# Main.net
KiCad netlist of a schematic drawn in Altium Designer
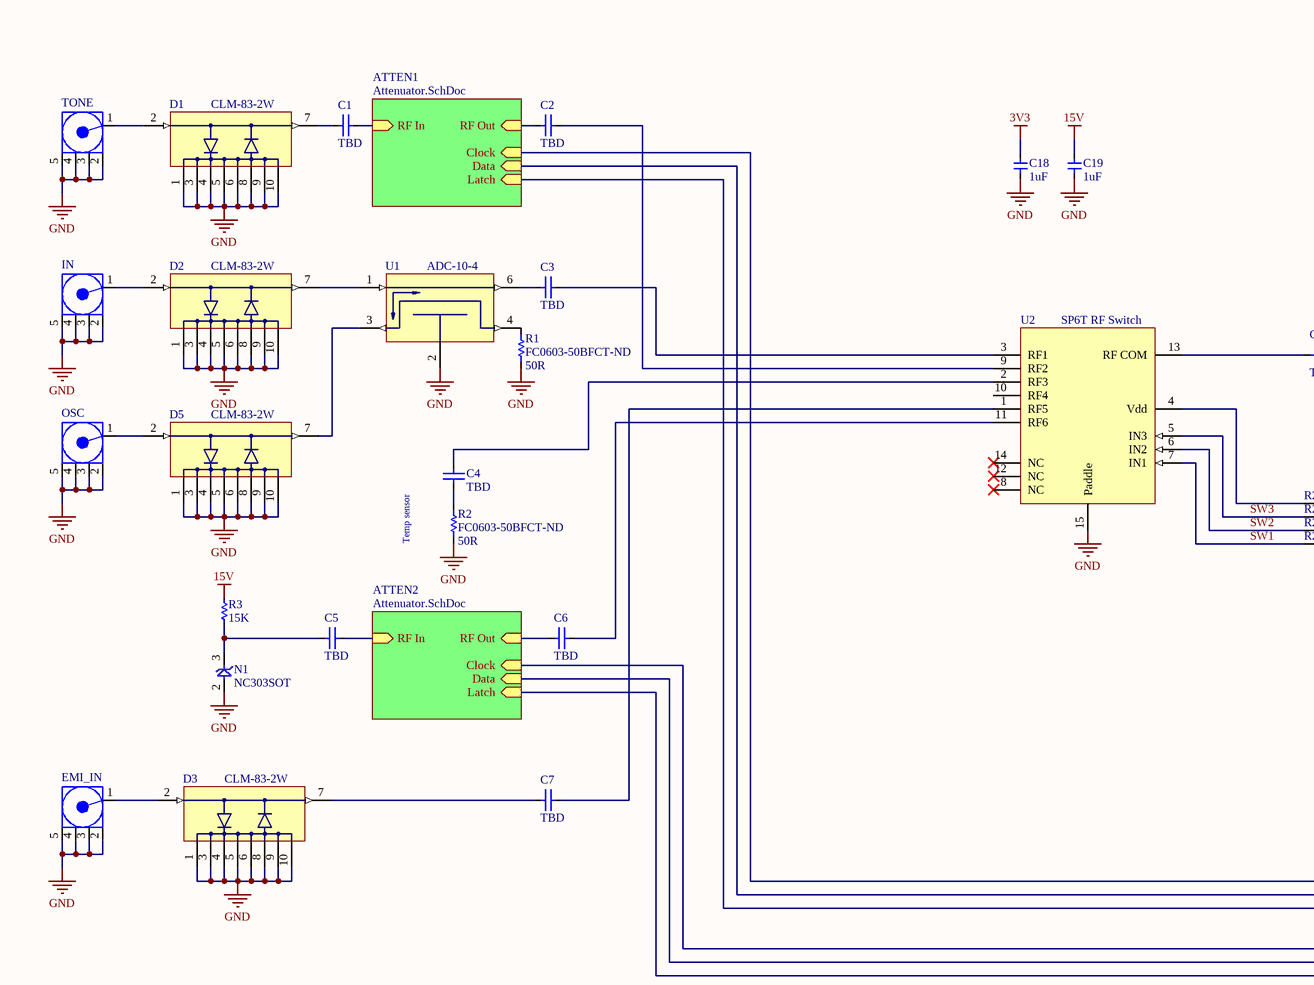
[diagram p0: Main.SchDoc, left]
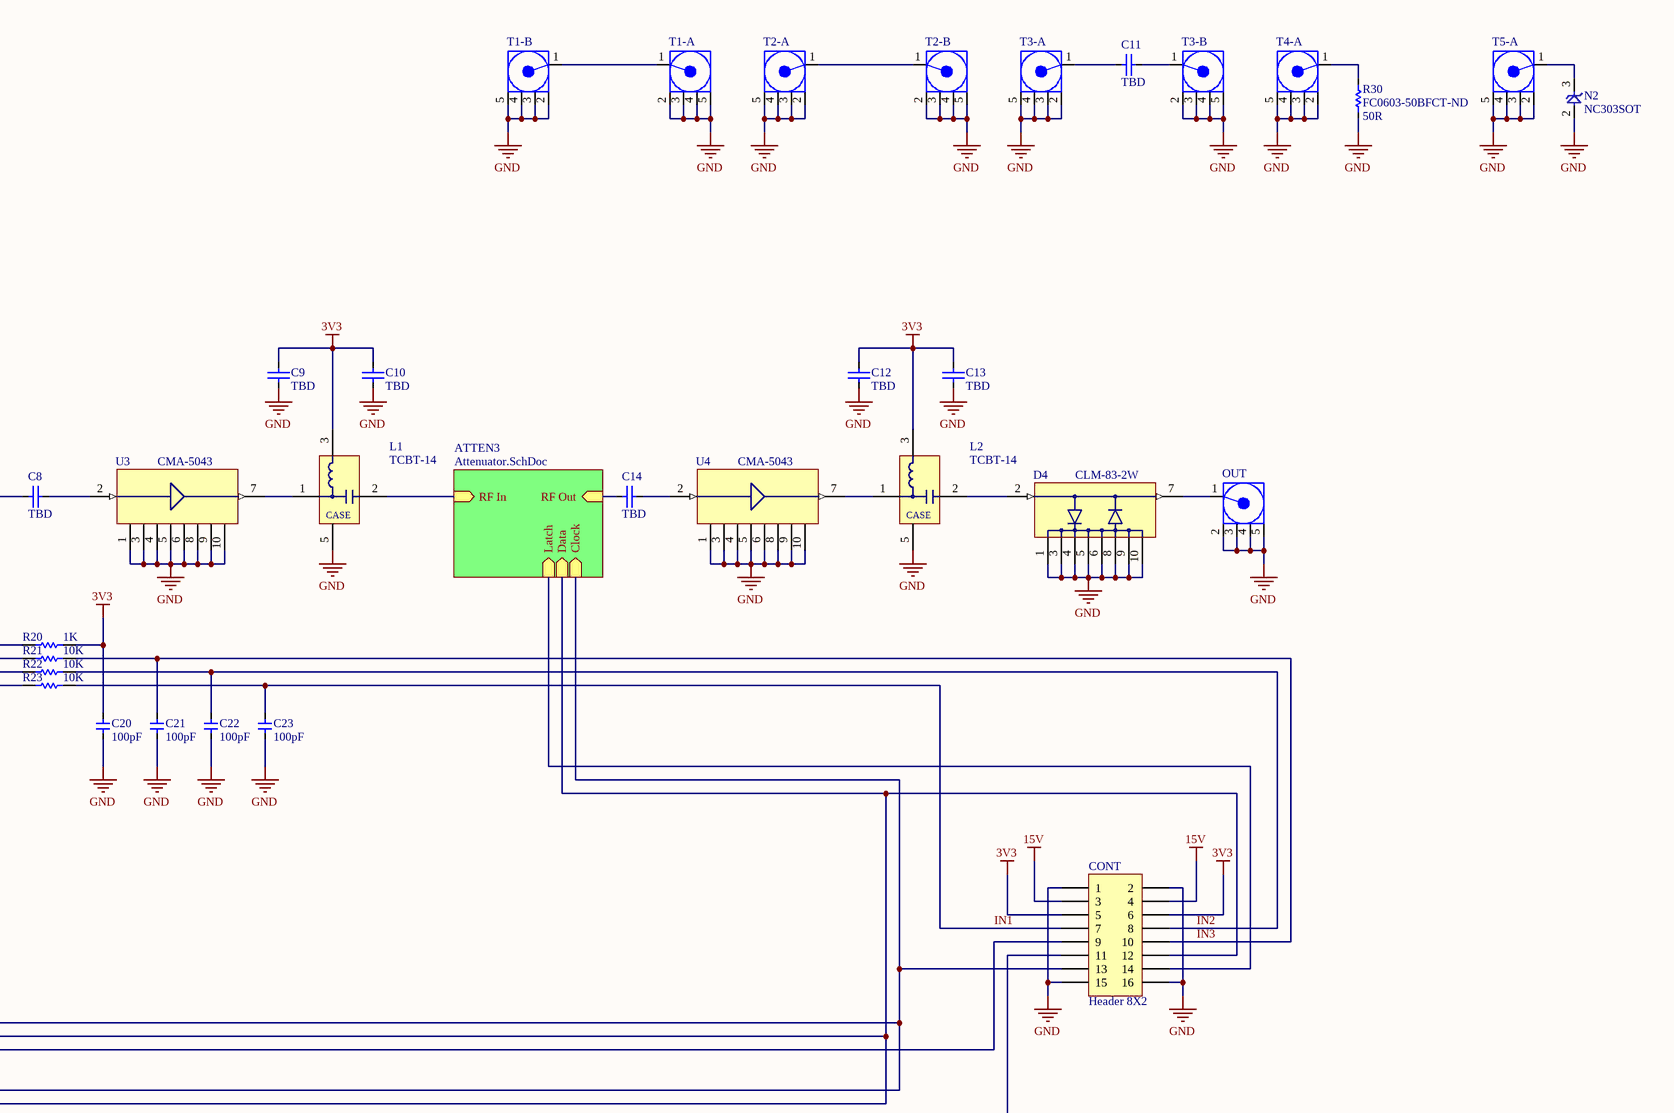
[diagram p1: Main.SchDoc, right]

(export (version "E")
  (design (tool "Eeschema 10.0.6"))
  (components
    (comp (ref "C1")
      (value "TBD")
      (footprint "0402C")
      (description "Capacitor")
      (fields (field (name "Comment") "Cap") (field (name "PUBLISHER") "Altium Limited"))
      (libsource (lib "Miscellaneous Devices") (part "Cap"))
    )
    (comp (ref "C2")
      (value "TBD")
      (footprint "0402C")
      (description "Capacitor")
      (fields (field (name "Comment") "Cap") (field (name "PUBLISHER") "Altium Limited"))
      (libsource (lib "Miscellaneous Devices") (part "Cap"))
    )
    (comp (ref "C3")
      (value "TBD")
      (footprint "0402C")
      (description "Capacitor")
      (fields (field (name "Comment") "Cap") (field (name "PUBLISHER") "Altium Limited"))
      (libsource (lib "Miscellaneous Devices") (part "Cap"))
    )
    (comp (ref "C4")
      (value "TBD")
      (footprint "0402C")
      (description "Capacitor")
      (fields (field (name "Comment") "Cap") (field (name "PUBLISHER") "Altium Limited"))
      (libsource (lib "Miscellaneous Devices") (part "Cap"))
    )
    (comp (ref "C5")
      (value "TBD")
      (footprint "0402C")
      (description "Capacitor")
      (fields (field (name "Comment") "Cap") (field (name "PUBLISHER") "Altium Limited"))
      (libsource (lib "Miscellaneous Devices") (part "Cap"))
    )
    (comp (ref "C6")
      (value "TBD")
      (footprint "0402C")
      (description "Capacitor")
      (fields (field (name "Comment") "Cap") (field (name "PUBLISHER") "Altium Limited"))
      (libsource (lib "Miscellaneous Devices") (part "Cap"))
    )
    (comp (ref "C7")
      (value "TBD")
      (footprint "0402C")
      (description "Capacitor")
      (fields (field (name "Comment") "Cap") (field (name "PUBLISHER") "Altium Limited"))
      (libsource (lib "Miscellaneous Devices") (part "Cap"))
    )
    (comp (ref "C8")
      (value "TBD")
      (footprint "0402C")
      (description "Capacitor")
      (fields (field (name "Comment") "Cap") (field (name "PUBLISHER") "Altium Limited"))
      (libsource (lib "Miscellaneous Devices") (part "Cap"))
    )
    (comp (ref "C9")
      (value "TBD")
      (footprint "0805C")
      (description "Capacitor")
      (fields (field (name "Comment") "Cap") (field (name "PUBLISHER") "Altium Limited"))
      (libsource (lib "Miscellaneous Devices") (part "Cap"))
    )
    (comp (ref "C10")
      (value "TBD")
      (footprint "0805C")
      (description "Capacitor")
      (fields (field (name "Comment") "Cap") (field (name "PUBLISHER") "Altium Limited"))
      (libsource (lib "Miscellaneous Devices") (part "Cap"))
    )
    (comp (ref "C11")
      (value "TBD")
      (footprint "0402C")
      (description "Capacitor")
      (fields (field (name "Comment") "Cap") (field (name "PUBLISHER") "Altium Limited"))
      (libsource (lib "Miscellaneous Devices") (part "Cap"))
    )
    (comp (ref "C12")
      (value "TBD")
      (footprint "0805C")
      (description "Capacitor")
      (fields (field (name "Comment") "Cap") (field (name "PUBLISHER") "Altium Limited"))
      (libsource (lib "Miscellaneous Devices") (part "Cap"))
    )
    (comp (ref "C13")
      (value "TBD")
      (footprint "0805C")
      (description "Capacitor")
      (fields (field (name "Comment") "Cap") (field (name "PUBLISHER") "Altium Limited"))
      (libsource (lib "Miscellaneous Devices") (part "Cap"))
    )
    (comp (ref "C14")
      (value "TBD")
      (footprint "0402C")
      (description "Capacitor")
      (fields (field (name "Comment") "Cap") (field (name "PUBLISHER") "Altium Limited"))
      (libsource (lib "Miscellaneous Devices") (part "Cap"))
    )
    (comp (ref "C18")
      (value "1uF")
      (footprint "V")
      (description "SMT Cap")
      (fields (field (name "PUBLISHER") "Altium Limited"))
      (libsource (lib "Miscellaneous Devices") (part "Cap - SMT Small"))
    )
    (comp (ref "C19")
      (value "1uF")
      (footprint "V")
      (description "SMT Cap")
      (fields (field (name "PUBLISHER") "Altium Limited"))
      (libsource (lib "Miscellaneous Devices") (part "Cap - SMT Small"))
    )
    (comp (ref "C20")
      (value "100pF")
      (footprint "0603C")
      (description "SMT Cap")
      (fields (field (name "PUBLISHER") "Altium Limited"))
      (libsource (lib "Miscellaneous Devices") (part "Cap - SMT Small"))
    )
    (comp (ref "C21")
      (value "100pF")
      (footprint "0603C")
      (description "SMT Cap")
      (fields (field (name "PUBLISHER") "Altium Limited"))
      (libsource (lib "Miscellaneous Devices") (part "Cap - SMT Small"))
    )
    (comp (ref "C22")
      (value "100pF")
      (footprint "0603C")
      (description "SMT Cap")
      (fields (field (name "PUBLISHER") "Altium Limited"))
      (libsource (lib "Miscellaneous Devices") (part "Cap - SMT Small"))
    )
    (comp (ref "C23")
      (value "100pF")
      (footprint "0603C")
      (description "SMT Cap")
      (fields (field (name "PUBLISHER") "Altium Limited"))
      (libsource (lib "Miscellaneous Devices") (part "Cap - SMT Small"))
    )
    (comp (ref "CONT")
      (value "Header 8X2")
      (footprint "SMT 16-pin rectangular header")
      (description "Header, 8-Pin, Dual row")
      (fields (field (name "PUBLISHER") "Altium Limited"))
      (libsource (lib "Miscellaneous Connectors") (part "Header 8X2"))
    )
    (comp (ref "D1")
      (value "CLM-83-2W")
      (footprint "DL1721")
      (description "+12 to +32 dBm RF Limiter")
      (libsource (lib "RF Components") (part "CLM-83-2W"))
    )
    (comp (ref "D2")
      (value "CLM-83-2W")
      (footprint "DL1721")
      (description "+12 to +32 dBm RF Limiter")
      (libsource (lib "RF Components") (part "CLM-83-2W"))
    )
    (comp (ref "D3")
      (value "CLM-83-2W")
      (footprint "DL1721")
      (description "+12 to +32 dBm RF Limiter")
      (libsource (lib "RF Components") (part "CLM-83-2W"))
    )
    (comp (ref "D4")
      (value "CLM-83-2W")
      (footprint "DL1721")
      (description "+12 to +32 dBm RF Limiter")
      (libsource (lib "RF Components") (part "CLM-83-2W"))
    )
    (comp (ref "D5")
      (value "CLM-83-2W")
      (footprint "DL1721")
      (description "+12 to +32 dBm RF Limiter")
      (libsource (lib "RF Components") (part "CLM-83-2W"))
    )
    (comp (ref "EMI_IN")
      (value "COAX-M")
      (footprint "SMT RA SMA Connector")
      (description "RF Coaxial PCB Connector, MMCX; Thru-Hole, Vertical Mount Plug,  50 Ohm Impedance")
      (fields (field (name "PUBLISHER") "Altium Limited"))
      (libsource (lib "Miscellaneous Connectors") (part "COAX-M"))
    )
    (comp (ref "IN")
      (value "COAX-M")
      (footprint "SMT RA SMA Connector")
      (description "RF Coaxial PCB Connector, MMCX; Thru-Hole, Vertical Mount Plug,  50 Ohm Impedance")
      (fields (field (name "PUBLISHER") "Altium Limited"))
      (libsource (lib "Miscellaneous Connectors") (part "COAX-M"))
    )
    (comp (ref "L1")
      (value "TCBT-14")
      (footprint "GU1414")
      (description "Surface Mount 10 MHz to 10 GHz Bias Tee")
      (libsource (lib "RF Components") (part "TCBT-14"))
    )
    (comp (ref "L2")
      (value "TCBT-14")
      (footprint "GU1414")
      (description "Surface Mount 10 MHz to 10 GHz Bias Tee")
      (libsource (lib "RF Components") (part "TCBT-14"))
    )
    (comp (ref "N1")
      (value "NC303SOT")
      (footprint "SOT323-3AN")
      (description "SMT Noise Diode")
      (libsource (lib "RF Components") (part "NC303SOT"))
    )
    (comp (ref "N2")
      (value "NC303SOT")
      (footprint "SOT323-3AN")
      (description "SMT Noise Diode")
      (libsource (lib "RF Components") (part "NC303SOT"))
    )
    (comp (ref "OSC")
      (value "COAX-M")
      (footprint "SMT RA SMA Connector")
      (description "RF Coaxial PCB Connector, MMCX; Thru-Hole, Vertical Mount Plug,  50 Ohm Impedance")
      (fields (field (name "PUBLISHER") "Altium Limited"))
      (libsource (lib "Miscellaneous Connectors") (part "COAX-M"))
    )
    (comp (ref "OUT")
      (value "COAX-M")
      (footprint "SMT RA SMA Connector")
      (description "RF Coaxial PCB Connector, MMCX; Thru-Hole, Vertical Mount Plug,  50 Ohm Impedance")
      (fields (field (name "PUBLISHER") "Altium Limited"))
      (libsource (lib "Miscellaneous Connectors") (part "COAX-M"))
    )
    (comp (ref "R1")
      (value "FC0603-50BFCT-ND")
      (footprint "0603R")
      (fields (field (name "ALTIUM_VALUE") "50R") (field (name "PUBLISHER") "Altium Limited"))
      (libsource (lib "Miscellaneous Devices") (part "Res Semi"))
    )
    (comp (ref "R2")
      (value "FC0603-50BFCT-ND")
      (footprint "0603R")
      (fields (field (name "ALTIUM_VALUE") "50R") (field (name "PUBLISHER") "Altium Limited"))
      (libsource (lib "Miscellaneous Devices") (part "Res Semi"))
    )
    (comp (ref "R3")
      (value "15K")
      (footprint "1206R")
      (description "Semiconductor Resistor")
      (fields (field (name "Comment") "Res Semi Small") (field (name "PUBLISHER") "Altium Limited"))
      (libsource (lib "Miscellaneous Devices") (part "Res Semi Small"))
    )
    (comp (ref "R20")
      (value "1K")
      (footprint "0603R")
      (description "Semiconductor Resistor")
      (fields (field (name "Comment") "RES Semi") (field (name "PUBLISHER") "Altium Limited"))
      (libsource (lib "") (part "Res Semi_1"))
    )
    (comp (ref "R21")
      (value "10K")
      (footprint "0603R")
      (description "Semiconductor Resistor")
      (fields (field (name "Comment") "RES Semi") (field (name "PUBLISHER") "Altium Limited"))
      (libsource (lib "") (part "Res Semi_1"))
    )
    (comp (ref "R22")
      (value "10K")
      (footprint "0603R")
      (description "Semiconductor Resistor")
      (fields (field (name "Comment") "RES Semi") (field (name "PUBLISHER") "Altium Limited"))
      (libsource (lib "") (part "Res Semi_1"))
    )
    (comp (ref "R23")
      (value "10K")
      (footprint "0603R")
      (description "Semiconductor Resistor")
      (fields (field (name "Comment") "RES Semi") (field (name "PUBLISHER") "Altium Limited"))
      (libsource (lib "") (part "Res Semi_1"))
    )
    (comp (ref "R30")
      (value "FC0603-50BFCT-ND")
      (footprint "0603R")
      (fields (field (name "ALTIUM_VALUE") "50R") (field (name "PUBLISHER") "Altium Limited"))
      (libsource (lib "Miscellaneous Devices") (part "Res Semi"))
    )
    (comp (ref "T1-A")
      (value "COAX-M")
      (footprint "SMT RA SMA Connector")
      (description "RF Coaxial PCB Connector, MMCX; Thru-Hole, Vertical Mount Plug,  50 Ohm Impedance")
      (fields (field (name "PUBLISHER") "Altium Limited"))
      (libsource (lib "Miscellaneous Connectors") (part "COAX-M"))
    )
    (comp (ref "T1-B")
      (value "COAX-M")
      (footprint "SMT RA SMA Connector")
      (description "RF Coaxial PCB Connector, MMCX; Thru-Hole, Vertical Mount Plug,  50 Ohm Impedance")
      (fields (field (name "PUBLISHER") "Altium Limited"))
      (libsource (lib "Miscellaneous Connectors") (part "COAX-M"))
    )
    (comp (ref "T2-A")
      (value "COAX-M")
      (footprint "SMT RA SMA Connector")
      (description "RF Coaxial PCB Connector, MMCX; Thru-Hole, Vertical Mount Plug,  50 Ohm Impedance")
      (fields (field (name "PUBLISHER") "Altium Limited"))
      (libsource (lib "Miscellaneous Connectors") (part "COAX-M"))
    )
    (comp (ref "T2-B")
      (value "COAX-M")
      (footprint "SMT RA SMA Connector")
      (description "RF Coaxial PCB Connector, MMCX; Thru-Hole, Vertical Mount Plug,  50 Ohm Impedance")
      (fields (field (name "PUBLISHER") "Altium Limited"))
      (libsource (lib "Miscellaneous Connectors") (part "COAX-M"))
    )
    (comp (ref "T3-A")
      (value "COAX-M")
      (footprint "SMT RA SMA Connector")
      (description "RF Coaxial PCB Connector, MMCX; Thru-Hole, Vertical Mount Plug,  50 Ohm Impedance")
      (fields (field (name "PUBLISHER") "Altium Limited"))
      (libsource (lib "Miscellaneous Connectors") (part "COAX-M"))
    )
    (comp (ref "T3-B")
      (value "COAX-M")
      (footprint "SMT RA SMA Connector")
      (description "RF Coaxial PCB Connector, MMCX; Thru-Hole, Vertical Mount Plug,  50 Ohm Impedance")
      (fields (field (name "PUBLISHER") "Altium Limited"))
      (libsource (lib "Miscellaneous Connectors") (part "COAX-M"))
    )
    (comp (ref "T4-A")
      (value "COAX-M")
      (footprint "SMT RA SMA Connector")
      (description "RF Coaxial PCB Connector, MMCX; Thru-Hole, Vertical Mount Plug,  50 Ohm Impedance")
      (fields (field (name "PUBLISHER") "Altium Limited"))
      (libsource (lib "Miscellaneous Connectors") (part "COAX-M"))
    )
    (comp (ref "T5-A")
      (value "COAX-M")
      (footprint "SMT RA SMA Connector")
      (description "RF Coaxial PCB Connector, MMCX; Thru-Hole, Vertical Mount Plug,  50 Ohm Impedance")
      (fields (field (name "PUBLISHER") "Altium Limited"))
      (libsource (lib "Miscellaneous Connectors") (part "COAX-M"))
    )
    (comp (ref "TONE")
      (value "COAX-M")
      (footprint "SMT RA SMA Connector")
      (description "RF Coaxial PCB Connector, MMCX; Thru-Hole, Vertical Mount Plug,  50 Ohm Impedance")
      (fields (field (name "PUBLISHER") "Altium Limited"))
      (libsource (lib "Miscellaneous Connectors") (part "COAX-M"))
    )
    (comp (ref "U1")
      (value "ADC-10-4")
      (footprint "CD542")
      (description "Surface Mount Directional Coupler")
      (libsource (lib "RF Components") (part "ADC-10-4"))
    )
    (comp (ref "U2")
      (value "SP6T RF Switch")
      (footprint "MT1817")
      (description "SP6T RF Switch 50Ω 10 to 2700 MHz")
      (libsource (lib "RF Components") (part "JSW6-33DR+"))
    )
    (comp (ref "U3")
      (value "CMA-5043")
      (footprint "DL1721")
      (description "Low Noise, High IP3 Monolithic Amplifier")
      (libsource (lib "RF Components") (part "CMA-5043"))
    )
    (comp (ref "U4")
      (value "CMA-5043")
      (footprint "DL1721")
      (description "Low Noise, High IP3 Monolithic Amplifier")
      (libsource (lib "RF Components") (part "CMA-5043"))
    )
  )
  (nets
    (net (code "1") (name "/Clock") (class "Default")
      (node (ref "CONT") (pin "13") (pinfunction "13_13") (pintype "passive"))
    )
    (net (code "2") (name "/Data") (class "Default")
      (node (ref "CONT") (pin "12") (pinfunction "12_12") (pintype "passive"))
    )
    (net (code "3") (name "/IN1") (class "Default")
      (node (ref "C23") (pin "2") (pinfunction "2_2") (pintype "passive"))
      (node (ref "CONT") (pin "7") (pinfunction "7_7") (pintype "passive"))
      (node (ref "R23") (pin "2") (pinfunction "2_2") (pintype "passive"))
    )
    (net (code "4") (name "/IN2") (class "Default")
      (node (ref "C22") (pin "2") (pinfunction "2_2") (pintype "passive"))
      (node (ref "CONT") (pin "8") (pinfunction "8_8") (pintype "passive"))
      (node (ref "R22") (pin "2") (pinfunction "2_2") (pintype "passive"))
    )
    (net (code "5") (name "/IN3") (class "Default")
      (node (ref "C21") (pin "2") (pinfunction "2_2") (pintype "passive"))
      (node (ref "CONT") (pin "10") (pinfunction "10_10") (pintype "passive"))
      (node (ref "R21") (pin "2") (pinfunction "2_2") (pintype "passive"))
    )
    (net (code "6") (name "/Latch") (class "Default")
      (node (ref "CONT") (pin "14") (pinfunction "14_14") (pintype "passive"))
    )
    (net (code "7") (name "/Latch_1") (class "Default")
      (node (ref "CONT") (pin "11") (pinfunction "11_11") (pintype "passive"))
    )
    (net (code "8") (name "/Latch_2") (class "Default")
      (node (ref "CONT") (pin "9") (pinfunction "9_9") (pintype "passive"))
    )
    (net (code "9") (name "/RF In") (class "Default")
      (node (ref "L1") (pin "2") (pinfunction "RF_2") (pintype "passive"))
    )
    (net (code "10") (name "/RF In_1") (class "Default")
      (node (ref "C5") (pin "2") (pinfunction "2_2") (pintype "passive"))
    )
    (net (code "11") (name "/RF In_2") (class "Default")
      (node (ref "C1") (pin "2") (pinfunction "2_2") (pintype "passive"))
    )
    (net (code "12") (name "/RF Out") (class "Default")
      (node (ref "C14") (pin "1") (pinfunction "1_1") (pintype "passive"))
    )
    (net (code "13") (name "/RF Out_1") (class "Default")
      (node (ref "C6") (pin "1") (pinfunction "1_1") (pintype "passive"))
    )
    (net (code "14") (name "/RF Out_2") (class "Default")
      (node (ref "C2") (pin "1") (pinfunction "1_1") (pintype "passive"))
    )
    (net (code "15") (name "/SW1") (class "Default")
      (node (ref "R23") (pin "1") (pinfunction "1_1") (pintype "passive"))
      (node (ref "U2") (pin "7") (pinfunction "IN1_7") (pintype "input"))
    )
    (net (code "16") (name "/SW2") (class "Default")
      (node (ref "R22") (pin "1") (pinfunction "1_1") (pintype "passive"))
      (node (ref "U2") (pin "6") (pinfunction "IN2_6") (pintype "input"))
    )
    (net (code "17") (name "/SW3") (class "Default")
      (node (ref "R21") (pin "1") (pinfunction "1_1") (pintype "passive"))
      (node (ref "U2") (pin "5") (pinfunction "IN3_5") (pintype "input"))
    )
    (net (code "18") (name "3V3") (class "Default")
      (node (ref "C10") (pin "2") (pinfunction "2_2") (pintype "passive"))
      (node (ref "C12") (pin "2") (pinfunction "2_2") (pintype "passive"))
      (node (ref "C13") (pin "2") (pinfunction "2_2") (pintype "passive"))
      (node (ref "C18") (pin "1") (pinfunction "1_1") (pintype "passive"))
      (node (ref "C20") (pin "2") (pinfunction "2_2") (pintype "passive"))
      (node (ref "C9") (pin "2") (pinfunction "2_2") (pintype "passive"))
      (node (ref "CONT") (pin "5") (pinfunction "5_5") (pintype "passive"))
      (node (ref "CONT") (pin "6") (pinfunction "6_6") (pintype "passive"))
      (node (ref "L1") (pin "3") (pinfunction "DC_3") (pintype "passive"))
      (node (ref "L2") (pin "3") (pinfunction "DC_3") (pintype "passive"))
      (node (ref "R20") (pin "2") (pinfunction "2_2") (pintype "passive"))
    )
    (net (code "19") (name "15V") (class "Default")
      (node (ref "C19") (pin "1") (pinfunction "1_1") (pintype "passive"))
      (node (ref "CONT") (pin "3") (pinfunction "3_3") (pintype "passive"))
      (node (ref "CONT") (pin "4") (pinfunction "4_4") (pintype "passive"))
      (node (ref "R3") (pin "2") (pinfunction "2_2") (pintype "passive"))
    )
    (net (code "20") (name "GND") (class "Default")
      (node (ref "C10") (pin "1") (pinfunction "1_1") (pintype "passive"))
      (node (ref "C12") (pin "1") (pinfunction "1_1") (pintype "passive"))
      (node (ref "C13") (pin "1") (pinfunction "1_1") (pintype "passive"))
      (node (ref "C18") (pin "2") (pinfunction "2_2") (pintype "passive"))
      (node (ref "C19") (pin "2") (pinfunction "2_2") (pintype "passive"))
      (node (ref "C20") (pin "1") (pinfunction "1_1") (pintype "passive"))
      (node (ref "C21") (pin "1") (pinfunction "1_1") (pintype "passive"))
      (node (ref "C22") (pin "1") (pinfunction "1_1") (pintype "passive"))
      (node (ref "C23") (pin "1") (pinfunction "1_1") (pintype "passive"))
      (node (ref "C9") (pin "1") (pinfunction "1_1") (pintype "passive"))
      (node (ref "CONT") (pin "1") (pinfunction "1_1") (pintype "passive"))
      (node (ref "CONT") (pin "15") (pinfunction "15_15") (pintype "passive"))
      (node (ref "CONT") (pin "16") (pinfunction "16_16") (pintype "passive"))
      (node (ref "CONT") (pin "2") (pinfunction "2_2") (pintype "passive"))
      (node (ref "D1") (pin "1") (pinfunction "Gnd_1") (pintype "passive"))
      (node (ref "D1") (pin "10") (pinfunction "Gnd_10") (pintype "power_in"))
      (node (ref "D1") (pin "3") (pinfunction "Gnd_3") (pintype "power_in"))
      (node (ref "D1") (pin "4") (pinfunction "Gnd_4") (pintype "power_in"))
      (node (ref "D1") (pin "5") (pinfunction "Gnd_5") (pintype "power_in"))
      (node (ref "D1") (pin "6") (pinfunction "Gnd_6") (pintype "power_in"))
      (node (ref "D1") (pin "8") (pinfunction "Gnd_8") (pintype "power_in"))
      (node (ref "D1") (pin "9") (pinfunction "Gnd_9") (pintype "power_in"))
      (node (ref "D2") (pin "1") (pinfunction "Gnd_1") (pintype "passive"))
      (node (ref "D2") (pin "10") (pinfunction "Gnd_10") (pintype "power_in"))
      (node (ref "D2") (pin "3") (pinfunction "Gnd_3") (pintype "power_in"))
      (node (ref "D2") (pin "4") (pinfunction "Gnd_4") (pintype "power_in"))
      (node (ref "D2") (pin "5") (pinfunction "Gnd_5") (pintype "power_in"))
      (node (ref "D2") (pin "6") (pinfunction "Gnd_6") (pintype "power_in"))
      (node (ref "D2") (pin "8") (pinfunction "Gnd_8") (pintype "power_in"))
      (node (ref "D2") (pin "9") (pinfunction "Gnd_9") (pintype "power_in"))
      (node (ref "D3") (pin "1") (pinfunction "Gnd_1") (pintype "passive"))
      (node (ref "D3") (pin "10") (pinfunction "Gnd_10") (pintype "power_in"))
      (node (ref "D3") (pin "3") (pinfunction "Gnd_3") (pintype "power_in"))
      (node (ref "D3") (pin "4") (pinfunction "Gnd_4") (pintype "power_in"))
      (node (ref "D3") (pin "5") (pinfunction "Gnd_5") (pintype "power_in"))
      (node (ref "D3") (pin "6") (pinfunction "Gnd_6") (pintype "power_in"))
      (node (ref "D3") (pin "8") (pinfunction "Gnd_8") (pintype "power_in"))
      (node (ref "D3") (pin "9") (pinfunction "Gnd_9") (pintype "power_in"))
      (node (ref "D4") (pin "1") (pinfunction "Gnd_1") (pintype "passive"))
      (node (ref "D4") (pin "10") (pinfunction "Gnd_10") (pintype "power_in"))
      (node (ref "D4") (pin "3") (pinfunction "Gnd_3") (pintype "power_in"))
      (node (ref "D4") (pin "4") (pinfunction "Gnd_4") (pintype "power_in"))
      (node (ref "D4") (pin "5") (pinfunction "Gnd_5") (pintype "power_in"))
      (node (ref "D4") (pin "6") (pinfunction "Gnd_6") (pintype "power_in"))
      (node (ref "D4") (pin "8") (pinfunction "Gnd_8") (pintype "power_in"))
      (node (ref "D4") (pin "9") (pinfunction "Gnd_9") (pintype "power_in"))
      (node (ref "D5") (pin "1") (pinfunction "Gnd_1") (pintype "passive"))
      (node (ref "D5") (pin "10") (pinfunction "Gnd_10") (pintype "power_in"))
      (node (ref "D5") (pin "3") (pinfunction "Gnd_3") (pintype "power_in"))
      (node (ref "D5") (pin "4") (pinfunction "Gnd_4") (pintype "power_in"))
      (node (ref "D5") (pin "5") (pinfunction "Gnd_5") (pintype "power_in"))
      (node (ref "D5") (pin "6") (pinfunction "Gnd_6") (pintype "power_in"))
      (node (ref "D5") (pin "8") (pinfunction "Gnd_8") (pintype "power_in"))
      (node (ref "D5") (pin "9") (pinfunction "Gnd_9") (pintype "power_in"))
      (node (ref "EMI_IN") (pin "2") (pinfunction "GND_2") (pintype "power_in"))
      (node (ref "EMI_IN") (pin "3") (pinfunction "GND_3") (pintype "power_in"))
      (node (ref "EMI_IN") (pin "4") (pinfunction "GND_4") (pintype "power_in"))
      (node (ref "EMI_IN") (pin "5") (pinfunction "GND_5") (pintype "power_in"))
      (node (ref "IN") (pin "2") (pinfunction "GND_2") (pintype "power_in"))
      (node (ref "IN") (pin "3") (pinfunction "GND_3") (pintype "power_in"))
      (node (ref "IN") (pin "4") (pinfunction "GND_4") (pintype "power_in"))
      (node (ref "IN") (pin "5") (pinfunction "GND_5") (pintype "power_in"))
      (node (ref "L1") (pin "5") (pinfunction "CASE_5") (pintype "passive"))
      (node (ref "L2") (pin "5") (pinfunction "CASE_5") (pintype "passive"))
      (node (ref "N1") (pin "2") (pinfunction "A_2") (pintype "passive"))
      (node (ref "N2") (pin "2") (pinfunction "A_2") (pintype "passive"))
      (node (ref "OSC") (pin "2") (pinfunction "GND_2") (pintype "power_in"))
      (node (ref "OSC") (pin "3") (pinfunction "GND_3") (pintype "power_in"))
      (node (ref "OSC") (pin "4") (pinfunction "GND_4") (pintype "power_in"))
      (node (ref "OSC") (pin "5") (pinfunction "GND_5") (pintype "power_in"))
      (node (ref "OUT") (pin "2") (pinfunction "GND_2") (pintype "power_in"))
      (node (ref "OUT") (pin "3") (pinfunction "GND_3") (pintype "power_in"))
      (node (ref "OUT") (pin "4") (pinfunction "GND_4") (pintype "power_in"))
      (node (ref "OUT") (pin "5") (pinfunction "GND_5") (pintype "power_in"))
      (node (ref "R1") (pin "1") (pinfunction "1_1") (pintype "passive"))
      (node (ref "R2") (pin "1") (pinfunction "1_1") (pintype "passive"))
      (node (ref "R30") (pin "1") (pinfunction "1_1") (pintype "passive"))
      (node (ref "T1-A") (pin "2") (pinfunction "GND_2") (pintype "power_in"))
      (node (ref "T1-A") (pin "3") (pinfunction "GND_3") (pintype "power_in"))
      (node (ref "T1-A") (pin "4") (pinfunction "GND_4") (pintype "power_in"))
      (node (ref "T1-A") (pin "5") (pinfunction "GND_5") (pintype "power_in"))
      (node (ref "T1-B") (pin "2") (pinfunction "GND_2") (pintype "power_in"))
      (node (ref "T1-B") (pin "3") (pinfunction "GND_3") (pintype "power_in"))
      (node (ref "T1-B") (pin "4") (pinfunction "GND_4") (pintype "power_in"))
      (node (ref "T1-B") (pin "5") (pinfunction "GND_5") (pintype "power_in"))
      (node (ref "T2-A") (pin "2") (pinfunction "GND_2") (pintype "power_in"))
      (node (ref "T2-A") (pin "3") (pinfunction "GND_3") (pintype "power_in"))
      (node (ref "T2-A") (pin "4") (pinfunction "GND_4") (pintype "power_in"))
      (node (ref "T2-A") (pin "5") (pinfunction "GND_5") (pintype "power_in"))
      (node (ref "T2-B") (pin "2") (pinfunction "GND_2") (pintype "power_in"))
      (node (ref "T2-B") (pin "3") (pinfunction "GND_3") (pintype "power_in"))
      (node (ref "T2-B") (pin "4") (pinfunction "GND_4") (pintype "power_in"))
      (node (ref "T2-B") (pin "5") (pinfunction "GND_5") (pintype "power_in"))
      (node (ref "T3-A") (pin "2") (pinfunction "GND_2") (pintype "power_in"))
      (node (ref "T3-A") (pin "3") (pinfunction "GND_3") (pintype "power_in"))
      (node (ref "T3-A") (pin "4") (pinfunction "GND_4") (pintype "power_in"))
      (node (ref "T3-A") (pin "5") (pinfunction "GND_5") (pintype "power_in"))
      (node (ref "T3-B") (pin "2") (pinfunction "GND_2") (pintype "power_in"))
      (node (ref "T3-B") (pin "3") (pinfunction "GND_3") (pintype "power_in"))
      (node (ref "T3-B") (pin "4") (pinfunction "GND_4") (pintype "power_in"))
      (node (ref "T3-B") (pin "5") (pinfunction "GND_5") (pintype "power_in"))
      (node (ref "T4-A") (pin "2") (pinfunction "GND_2") (pintype "power_in"))
      (node (ref "T4-A") (pin "3") (pinfunction "GND_3") (pintype "power_in"))
      (node (ref "T4-A") (pin "4") (pinfunction "GND_4") (pintype "power_in"))
      (node (ref "T4-A") (pin "5") (pinfunction "GND_5") (pintype "power_in"))
      (node (ref "T5-A") (pin "2") (pinfunction "GND_2") (pintype "power_in"))
      (node (ref "T5-A") (pin "3") (pinfunction "GND_3") (pintype "power_in"))
      (node (ref "T5-A") (pin "4") (pinfunction "GND_4") (pintype "power_in"))
      (node (ref "T5-A") (pin "5") (pinfunction "GND_5") (pintype "power_in"))
      (node (ref "TONE") (pin "2") (pinfunction "GND_2") (pintype "power_in"))
      (node (ref "TONE") (pin "3") (pinfunction "GND_3") (pintype "power_in"))
      (node (ref "TONE") (pin "4") (pinfunction "GND_4") (pintype "power_in"))
      (node (ref "TONE") (pin "5") (pinfunction "GND_5") (pintype "power_in"))
      (node (ref "U1") (pin "2") (pinfunction "Gnd_2") (pintype "power_in"))
      (node (ref "U2") (pin "15") (pinfunction "Paddle_15") (pintype "power_in"))
      (node (ref "U3") (pin "1") (pinfunction "Gnd_1") (pintype "passive"))
      (node (ref "U3") (pin "10") (pinfunction "Gnd_10") (pintype "power_in"))
      (node (ref "U3") (pin "3") (pinfunction "Gnd_3") (pintype "power_in"))
      (node (ref "U3") (pin "4") (pinfunction "Gnd_4") (pintype "power_in"))
      (node (ref "U3") (pin "5") (pinfunction "Gnd_5") (pintype "power_in"))
      (node (ref "U3") (pin "6") (pinfunction "Gnd_6") (pintype "power_in"))
      (node (ref "U3") (pin "8") (pinfunction "Gnd_8") (pintype "power_in"))
      (node (ref "U3") (pin "9") (pinfunction "Gnd_9") (pintype "power_in"))
      (node (ref "U4") (pin "1") (pinfunction "Gnd_1") (pintype "passive"))
      (node (ref "U4") (pin "10") (pinfunction "Gnd_10") (pintype "power_in"))
      (node (ref "U4") (pin "3") (pinfunction "Gnd_3") (pintype "power_in"))
      (node (ref "U4") (pin "4") (pinfunction "Gnd_4") (pintype "power_in"))
      (node (ref "U4") (pin "5") (pinfunction "Gnd_5") (pintype "power_in"))
      (node (ref "U4") (pin "6") (pinfunction "Gnd_6") (pintype "power_in"))
      (node (ref "U4") (pin "8") (pinfunction "Gnd_8") (pintype "power_in"))
      (node (ref "U4") (pin "9") (pinfunction "Gnd_9") (pintype "power_in"))
    )
    (net (code "21") (name "Net-(C1-Pad1)") (class "Default")
      (node (ref "C1") (pin "1") (pinfunction "1_1") (pintype "passive"))
      (node (ref "D1") (pin "7") (pinfunction "Gnd_7") (pintype "output"))
    )
    (net (code "22") (name "Net-(C4-Pad1)") (class "Default")
      (node (ref "C4") (pin "1") (pinfunction "1_1") (pintype "passive"))
      (node (ref "R2") (pin "2") (pinfunction "2_2") (pintype "passive"))
    )
    (net (code "23") (name "Net-(C7-Pad1)") (class "Default")
      (node (ref "C7") (pin "1") (pinfunction "1_1") (pintype "passive"))
      (node (ref "D3") (pin "7") (pinfunction "Gnd_7") (pintype "output"))
    )
    (net (code "24") (name "Net-(D1-In)") (class "Default")
      (node (ref "D1") (pin "2") (pinfunction "In_2") (pintype "input"))
      (node (ref "TONE") (pin "1") (pinfunction "Signal_1") (pintype "passive"))
    )
    (net (code "25") (name "Net-(D2-In)") (class "Default")
      (node (ref "D2") (pin "2") (pinfunction "In_2") (pintype "input"))
      (node (ref "IN") (pin "1") (pinfunction "Signal_1") (pintype "passive"))
    )
    (net (code "26") (name "Net-(D3-In)") (class "Default")
      (node (ref "D3") (pin "2") (pinfunction "In_2") (pintype "input"))
      (node (ref "EMI_IN") (pin "1") (pinfunction "Signal_1") (pintype "passive"))
    )
    (net (code "27") (name "Net-(D4-In)") (class "Default")
      (node (ref "D4") (pin "2") (pinfunction "In_2") (pintype "input"))
      (node (ref "L2") (pin "2") (pinfunction "RF_2") (pintype "passive"))
    )
    (net (code "28") (name "Net-(D5-In)") (class "Default")
      (node (ref "D5") (pin "2") (pinfunction "In_2") (pintype "input"))
      (node (ref "OSC") (pin "1") (pinfunction "Signal_1") (pintype "passive"))
    )
    (net (code "29") (name "Net-(L1-RF+DC)") (class "Default")
      (node (ref "L1") (pin "1") (pinfunction "RF+DC_1") (pintype "passive"))
      (node (ref "U3") (pin "7") (pinfunction "Gnd_7") (pintype "output"))
    )
    (net (code "30") (name "Net-(L2-RF+DC)") (class "Default")
      (node (ref "L2") (pin "1") (pinfunction "RF+DC_1") (pintype "passive"))
      (node (ref "U4") (pin "7") (pinfunction "Gnd_7") (pintype "output"))
    )
    (net (code "31") (name "Net-(N1-C)") (class "Default")
      (node (ref "C5") (pin "1") (pinfunction "1_1") (pintype "passive"))
      (node (ref "N1") (pin "3") (pinfunction "C_3") (pintype "passive"))
      (node (ref "R3") (pin "1") (pinfunction "1_1") (pintype "passive"))
    )
    (net (code "32") (name "Net-(N2-C)") (class "Default")
      (node (ref "N2") (pin "3") (pinfunction "C_3") (pintype "passive"))
      (node (ref "T5-A") (pin "1") (pinfunction "Signal_1") (pintype "passive"))
    )
    (net (code "33") (name "Net-(OUT-Signal)") (class "Default")
      (node (ref "D4") (pin "7") (pinfunction "Gnd_7") (pintype "output"))
      (node (ref "OUT") (pin "1") (pinfunction "Signal_1") (pintype "passive"))
    )
    (net (code "34") (name "Net-(T1-A-Signal)") (class "Default")
      (node (ref "T1-A") (pin "1") (pinfunction "Signal_1") (pintype "passive"))
      (node (ref "T1-B") (pin "1") (pinfunction "Signal_1") (pintype "passive"))
    )
    (net (code "35") (name "Net-(T2-A-Signal)") (class "Default")
      (node (ref "T2-A") (pin "1") (pinfunction "Signal_1") (pintype "passive"))
      (node (ref "T2-B") (pin "1") (pinfunction "Signal_1") (pintype "passive"))
    )
    (net (code "36") (name "Net-(T3-A-Signal)") (class "Default")
      (node (ref "C11") (pin "1") (pinfunction "1_1") (pintype "passive"))
      (node (ref "T3-A") (pin "1") (pinfunction "Signal_1") (pintype "passive"))
    )
    (net (code "37") (name "Net-(T3-B-Signal)") (class "Default")
      (node (ref "C11") (pin "2") (pinfunction "2_2") (pintype "passive"))
      (node (ref "T3-B") (pin "1") (pinfunction "Signal_1") (pintype "passive"))
    )
    (net (code "38") (name "Net-(T4-A-Signal)") (class "Default")
      (node (ref "R30") (pin "2") (pinfunction "2_2") (pintype "passive"))
      (node (ref "T4-A") (pin "1") (pinfunction "Signal_1") (pintype "passive"))
    )
    (net (code "39") (name "Net-(U1-Coupled)") (class "Default")
      (node (ref "D5") (pin "7") (pinfunction "Gnd_7") (pintype "output"))
      (node (ref "U1") (pin "3") (pinfunction "Coupled_3") (pintype "output"))
    )
    (net (code "40") (name "Net-(U1-Input)") (class "Default")
      (node (ref "D2") (pin "7") (pinfunction "Gnd_7") (pintype "output"))
      (node (ref "U1") (pin "1") (pinfunction "Input_1") (pintype "input"))
    )
    (net (code "41") (name "Net-(U1-Output)") (class "Default")
      (node (ref "C3") (pin "1") (pinfunction "1_1") (pintype "passive"))
      (node (ref "U1") (pin "6") (pinfunction "Output_6") (pintype "output"))
    )
    (net (code "42") (name "Net-(U1-Termination)") (class "Default")
      (node (ref "R1") (pin "2") (pinfunction "2_2") (pintype "passive"))
      (node (ref "U1") (pin "4") (pinfunction "Termination_4") (pintype "output"))
    )
    (net (code "43") (name "Net-(U2-RF1)") (class "Default")
      (node (ref "C3") (pin "2") (pinfunction "2_2") (pintype "passive"))
      (node (ref "U2") (pin "3") (pinfunction "RF1_3") (pintype "passive"))
    )
    (net (code "44") (name "Net-(U2-RF2)") (class "Default")
      (node (ref "C2") (pin "2") (pinfunction "2_2") (pintype "passive"))
      (node (ref "U2") (pin "9") (pinfunction "RF2_9") (pintype "passive"))
    )
    (net (code "45") (name "Net-(U2-RF3)") (class "Default")
      (node (ref "C4") (pin "2") (pinfunction "2_2") (pintype "passive"))
      (node (ref "U2") (pin "2") (pinfunction "RF3_2") (pintype "passive"))
    )
    (net (code "46") (name "Net-(U2-RF5)") (class "Default")
      (node (ref "C7") (pin "2") (pinfunction "2_2") (pintype "passive"))
      (node (ref "U2") (pin "1") (pinfunction "RF5_1") (pintype "passive"))
    )
    (net (code "47") (name "Net-(U2-RF6)") (class "Default")
      (node (ref "C6") (pin "2") (pinfunction "2_2") (pintype "passive"))
      (node (ref "U2") (pin "11") (pinfunction "RF6_11") (pintype "passive"))
    )
    (net (code "48") (name "Net-(U2-RF_COM)") (class "Default")
      (node (ref "C8") (pin "1") (pinfunction "1_1") (pintype "passive"))
      (node (ref "U2") (pin "13") (pinfunction "RF_COM_13") (pintype "passive"))
    )
    (net (code "49") (name "Net-(U2-Vdd)") (class "Default")
      (node (ref "R20") (pin "1") (pinfunction "1_1") (pintype "passive"))
      (node (ref "U2") (pin "4") (pinfunction "Vdd_4") (pintype "power_in"))
    )
    (net (code "50") (name "Net-(U3-In)") (class "Default")
      (node (ref "C8") (pin "2") (pinfunction "2_2") (pintype "passive"))
      (node (ref "U3") (pin "2") (pinfunction "In_2") (pintype "input"))
    )
    (net (code "51") (name "Net-(U4-In)") (class "Default")
      (node (ref "C14") (pin "2") (pinfunction "2_2") (pintype "passive"))
      (node (ref "U4") (pin "2") (pinfunction "In_2") (pintype "input"))
    )
    (net (code "52") (name "unconnected-(L1-NC-Pad4)") (class "Default")
      (node (ref "L1") (pin "4") (pinfunction "NC_4") (pintype "passive"))
    )
    (net (code "53") (name "unconnected-(L2-NC-Pad4)") (class "Default")
      (node (ref "L2") (pin "4") (pinfunction "NC_4") (pintype "passive"))
    )
    (net (code "54") (name "unconnected-(U1-DNC-Pad5)") (class "Default")
      (node (ref "U1") (pin "5") (pinfunction "DNC_5") (pintype "passive"))
    )
    (net (code "55") (name "unconnected-(U2-NC-Pad8)") (class "Default")
      (node (ref "U2") (pin "8") (pinfunction "NC_8") (pintype "passive+no_connect"))
    )
    (net (code "56") (name "unconnected-(U2-NC-Pad12)") (class "Default")
      (node (ref "U2") (pin "12") (pinfunction "NC_12") (pintype "passive+no_connect"))
    )
    (net (code "57") (name "unconnected-(U2-NC-Pad14)") (class "Default")
      (node (ref "U2") (pin "14") (pinfunction "NC_14") (pintype "passive+no_connect"))
    )
    (net (code "58") (name "unconnected-(U2-RF4-Pad10)") (class "Default")
      (node (ref "U2") (pin "10") (pinfunction "RF4_10") (pintype "passive"))
    )
  )
)
